# 05-UARTBridge.net
KiCad netlist of a schematic drawn in Altium Designer
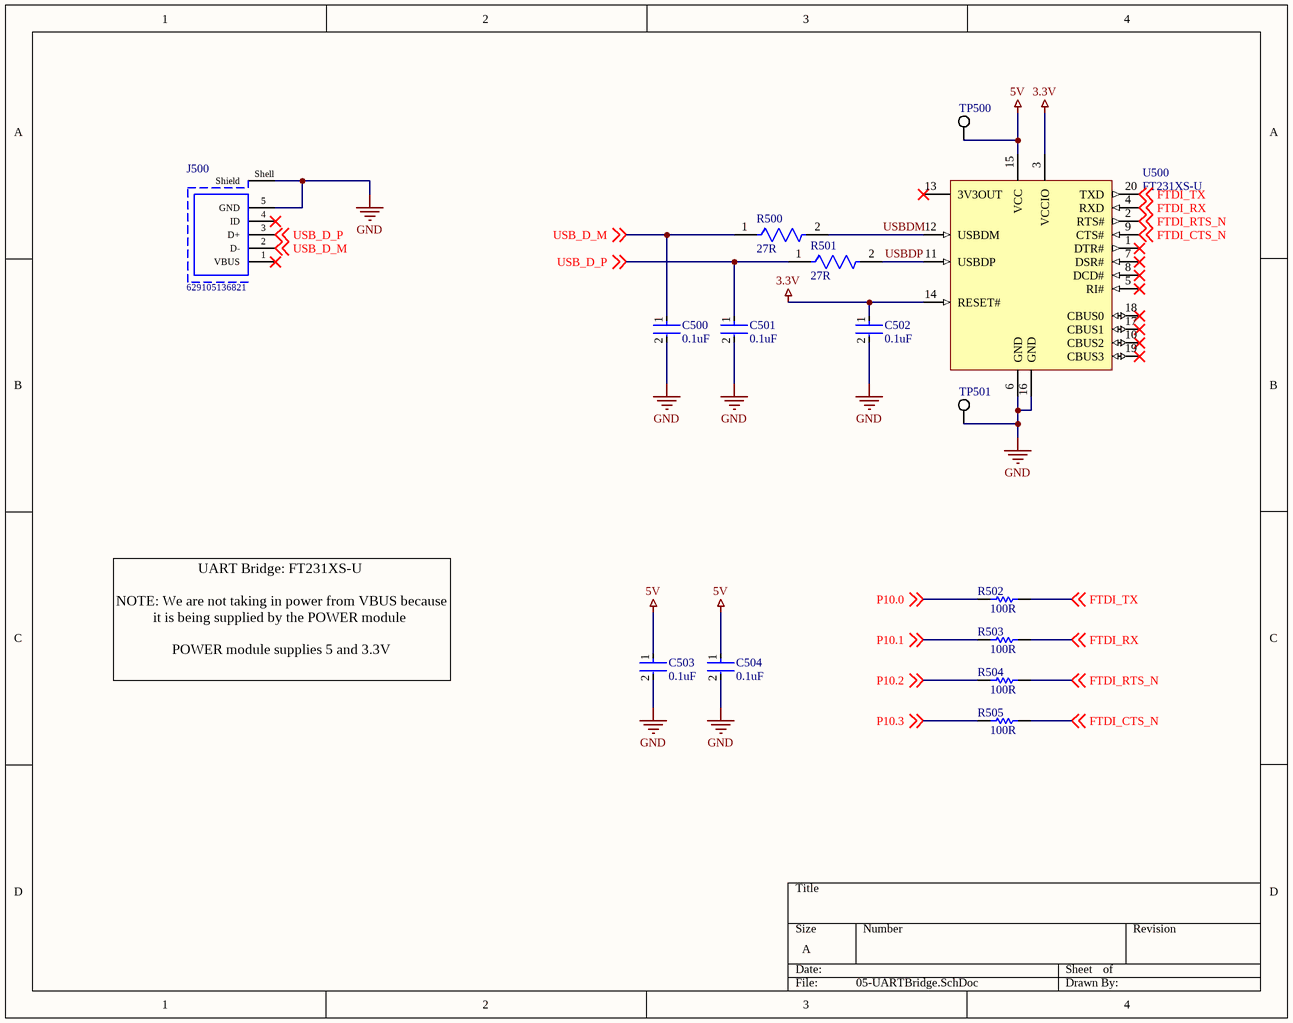
[diagram p0: 05-UARTBridge.SchDoc]

(export (version "E")
  (design (tool "Eeschema 10.0.6"))
  (components
    (comp (ref "C500")
      (value "0.1uF")
      (footprint "FP-CL21-IPC_C")
      (description "CL21 Series 0805 100nF 50V ±10% Tolerance X7R Multilayer Ceramic Chip Capacitor")
      (fields (field (name "TOLERANCE") "10%") (field (name "VOLTAGE") "50V"))
      (libsource (lib "Altium Content Vault") (part "b4654b650e69147ec39a6b967a45e02"))
    )
    (comp (ref "C501")
      (value "0.1uF")
      (footprint "FP-CL21-IPC_C")
      (description "CL21 Series 0805 100nF 50V ±10% Tolerance X7R Multilayer Ceramic Chip Capacitor")
      (fields (field (name "TOLERANCE") "10%") (field (name "VOLTAGE") "50V"))
      (libsource (lib "Altium Content Vault") (part "b4654b650e69147ec39a6b967a45e02"))
    )
    (comp (ref "C502")
      (value "0.1uF")
      (footprint "FP-CL21-IPC_C")
      (description "CL21 Series 0805 100nF 50V ±10% Tolerance X7R Multilayer Ceramic Chip Capacitor")
      (fields (field (name "TOLERANCE") "10%") (field (name "VOLTAGE") "50V"))
      (libsource (lib "Altium Content Vault") (part "b4654b650e69147ec39a6b967a45e02"))
    )
    (comp (ref "C503")
      (value "0.1uF")
      (footprint "FP-CL21-IPC_C")
      (description "CL21 Series 0805 100nF 50V ±10% Tolerance X7R Multilayer Ceramic Chip Capacitor")
      (fields (field (name "TOLERANCE") "10%") (field (name "VOLTAGE") "50V"))
      (libsource (lib "Altium Content Vault") (part "b4654b650e69147ec39a6b967a45e02"))
    )
    (comp (ref "C504")
      (value "0.1uF")
      (footprint "FP-CL21-IPC_C")
      (description "CL21 Series 0805 100nF 50V ±10% Tolerance X7R Multilayer Ceramic Chip Capacitor")
      (fields (field (name "TOLERANCE") "10%") (field (name "VOLTAGE") "50V"))
      (libsource (lib "Altium Content Vault") (part "b4654b650e69147ec39a6b967a45e02"))
    )
    (comp (ref "J500")
      (value "629105136821")
      (footprint "629105136821")
      (description "Micro USB 2.0 Type B Receptacle WR-COM, Horizontal, SMT, with Pads and Pegs")
      (fields (field (name "MANUFACTURER") "Wurth Elektronik") (field (name "PUBLISHER") "WurthElektronik"))
      (libsource (lib "Altium Content Vault") (part "WE-USB-5-1SHLD"))
    )
    (comp (ref "R500")
      (value "27R")
      (footprint "FP-CRGCQ0805-IPC_C")
      (description "CRGCQ0805 27Ω 0.125W ±200ppm/°C 1% 150V")
      (fields
        (field (name "MANUFACTURER") "TE Connectivity")
        (field (name "OCTOPART") "https://octopart.com/crgcq0805f27r-te+connectivity-91018166")
      )
      (libsource (lib "Altium Content Vault") (part "1029c3af85768c4190bb7ad29bc67b5"))
    )
    (comp (ref "R501")
      (value "27R")
      (footprint "FP-CRGCQ0805-IPC_C")
      (description "CRGCQ0805 27Ω 0.125W ±200ppm/°C 1% 150V")
      (fields
        (field (name "MANUFACTURER") "TE Connectivity")
        (field (name "OCTOPART") "https://octopart.com/crgcq0805f27r-te+connectivity-91018166")
      )
      (libsource (lib "Altium Content Vault") (part "1029c3af85768c4190bb7ad29bc67b5"))
    )
    (comp (ref "R502")
      (value "100R")
      (footprint "RESC2013X60X40ML20T25")
      (fields (field (name "MANUFACTURER") "Panasonic") (field (name "PART NUMBER") "ERA6AEB101V"))
      (libsource (lib "Altium Content Vault") (part "RES"))
    )
    (comp (ref "R503")
      (value "100R")
      (footprint "RESC2013X60X40ML20T25")
      (fields (field (name "MANUFACTURER") "Panasonic") (field (name "PART NUMBER") "ERA6AEB101V"))
      (libsource (lib "Altium Content Vault") (part "RES"))
    )
    (comp (ref "R504")
      (value "100R")
      (footprint "RESC2013X60X40ML20T25")
      (fields (field (name "MANUFACTURER") "Panasonic") (field (name "PART NUMBER") "ERA6AEB101V"))
      (libsource (lib "Altium Content Vault") (part "RES"))
    )
    (comp (ref "R505")
      (value "100R")
      (footprint "RESC2013X60X40ML20T25")
      (fields (field (name "MANUFACTURER") "Panasonic") (field (name "PART NUMBER") "ERA6AEB101V"))
      (libsource (lib "Altium Content Vault") (part "RES"))
    )
    (comp (ref "TP500")
      (value "5019")
      (footprint "KSTN-5019_V")
      (description "Test Point, 1 Position SMD, RoHS, Tape and Reel")
      (libsource (lib "Altium Content Vault") (part "TESTPOINT_WHITE"))
    )
    (comp (ref "TP501")
      (value "5019")
      (footprint "KSTN-5019_V")
      (description "Test Point, 1 Position SMD, RoHS, Tape and Reel")
      (libsource (lib "Altium Content Vault") (part "TESTPOINT_WHITE"))
    )
    (comp (ref "U500")
      (value "FT231XS-U")
      (footprint "SSOP-20_L")
      (fields (field (name "MANUFACTURER") "FTDI"))
      (libsource (lib "Altium Content Vault") (part "COM-USB-FT231XS-IL20"))
    )
  )
  (nets
    (net (code "1") (name "/USBDM") (class "Default")
      (node (ref "R500") (pin "2") (pinfunction "2_2") (pintype "passive"))
      (node (ref "U500") (pin "12") (pinfunction "USBDM_12") (pintype "input"))
    )
    (net (code "2") (name "/USBDP") (class "Default")
      (node (ref "R501") (pin "2") (pinfunction "2_2") (pintype "passive"))
      (node (ref "U500") (pin "11") (pinfunction "USBDP_11") (pintype "input"))
    )
    (net (code "3") (name "3.3V") (class "Default")
      (node (ref "C502") (pin "1") (pinfunction "1_1") (pintype "passive"))
      (node (ref "U500") (pin "14") (pinfunction "RESET#_14") (pintype "input"))
      (node (ref "U500") (pin "3") (pinfunction "VCCIO_3") (pintype "power_in"))
    )
    (net (code "4") (name "5V") (class "Default")
      (node (ref "C503") (pin "1") (pinfunction "1_1") (pintype "passive"))
      (node (ref "C504") (pin "1") (pinfunction "1_1") (pintype "passive"))
      (node (ref "TP500") (pin "1") (pinfunction "1_1") (pintype "passive"))
      (node (ref "U500") (pin "15") (pinfunction "VCC_15") (pintype "power_in"))
    )
    (net (code "5") (name "FTDI_CTS_N") (class "Default")
      (node (ref "R505") (pin "2") (pinfunction "2_2") (pintype "passive"))
      (node (ref "U500") (pin "9") (pinfunction "CTS#_9") (pintype "input"))
    )
    (net (code "6") (name "FTDI_RTS_N") (class "Default")
      (node (ref "R504") (pin "2") (pinfunction "2_2") (pintype "passive"))
      (node (ref "U500") (pin "2") (pinfunction "RTS#_2") (pintype "output"))
    )
    (net (code "7") (name "FTDI_RX") (class "Default")
      (node (ref "R503") (pin "2") (pinfunction "2_2") (pintype "passive"))
      (node (ref "U500") (pin "4") (pinfunction "RXD_4") (pintype "input"))
    )
    (net (code "8") (name "FTDI_TX") (class "Default")
      (node (ref "R502") (pin "2") (pinfunction "2_2") (pintype "passive"))
      (node (ref "U500") (pin "20") (pinfunction "TXD_20") (pintype "output"))
    )
    (net (code "9") (name "GND") (class "Default")
      (node (ref "C500") (pin "2") (pinfunction "2_2") (pintype "passive"))
      (node (ref "C501") (pin "2") (pinfunction "2_2") (pintype "passive"))
      (node (ref "C502") (pin "2") (pinfunction "2_2") (pintype "passive"))
      (node (ref "C503") (pin "2") (pinfunction "2_2") (pintype "passive"))
      (node (ref "C504") (pin "2") (pinfunction "2_2") (pintype "passive"))
      (node (ref "J500") (pin "5") (pinfunction "GND_5") (pintype "passive"))
      (node (ref "J500") (pin "Shell") (pinfunction "Shield_Shell") (pintype "passive"))
      (node (ref "TP501") (pin "1") (pinfunction "1_1") (pintype "passive"))
      (node (ref "U500") (pin "16") (pinfunction "GND_16") (pintype "power_in"))
      (node (ref "U500") (pin "6") (pinfunction "GND_6") (pintype "power_in"))
    )
    (net (code "10") (name "P10.0") (class "Default")
      (node (ref "R502") (pin "1") (pinfunction "1_1") (pintype "passive"))
    )
    (net (code "11") (name "P10.1") (class "Default")
      (node (ref "R503") (pin "1") (pinfunction "1_1") (pintype "passive"))
    )
    (net (code "12") (name "P10.2") (class "Default")
      (node (ref "R504") (pin "1") (pinfunction "1_1") (pintype "passive"))
    )
    (net (code "13") (name "P10.3") (class "Default")
      (node (ref "R505") (pin "1") (pinfunction "1_1") (pintype "passive"))
    )
    (net (code "14") (name "USB_D_M") (class "Default")
      (node (ref "C500") (pin "1") (pinfunction "1_1") (pintype "passive"))
      (node (ref "J500") (pin "2") (pinfunction "D-_2") (pintype "passive"))
      (node (ref "R500") (pin "1") (pinfunction "1_1") (pintype "passive"))
    )
    (net (code "15") (name "USB_D_P") (class "Default")
      (node (ref "C501") (pin "1") (pinfunction "1_1") (pintype "passive"))
      (node (ref "J500") (pin "3") (pinfunction "D+_3") (pintype "passive"))
      (node (ref "R501") (pin "1") (pinfunction "1_1") (pintype "passive"))
    )
    (net (code "16") (name "unconnected-(J500-ID-Pad4)") (class "Default")
      (node (ref "J500") (pin "4") (pinfunction "ID_4") (pintype "passive+no_connect"))
    )
    (net (code "17") (name "unconnected-(J500-VBUS-Pad1)") (class "Default")
      (node (ref "J500") (pin "1") (pinfunction "VBUS_1") (pintype "passive+no_connect"))
    )
    (net (code "18") (name "unconnected-(U500-3V3OUT-Pad13)") (class "Default")
      (node (ref "U500") (pin "13") (pinfunction "3V3OUT_13") (pintype "power_in+no_connect"))
    )
    (net (code "19") (name "unconnected-(U500-CBUS0-Pad18)") (class "Default")
      (node (ref "U500") (pin "18") (pinfunction "CBUS0_18") (pintype "bidirectional+no_connect"))
    )
    (net (code "20") (name "unconnected-(U500-CBUS1-Pad17)") (class "Default")
      (node (ref "U500") (pin "17") (pinfunction "CBUS1_17") (pintype "bidirectional+no_connect"))
    )
    (net (code "21") (name "unconnected-(U500-CBUS2-Pad10)") (class "Default")
      (node (ref "U500") (pin "10") (pinfunction "CBUS2_10") (pintype "bidirectional+no_connect"))
    )
    (net (code "22") (name "unconnected-(U500-CBUS3-Pad19)") (class "Default")
      (node (ref "U500") (pin "19") (pinfunction "CBUS3_19") (pintype "bidirectional+no_connect"))
    )
    (net (code "23") (name "unconnected-(U500-DCD#-Pad8)") (class "Default")
      (node (ref "U500") (pin "8") (pinfunction "DCD#_8") (pintype "input+no_connect"))
    )
    (net (code "24") (name "unconnected-(U500-DSR#-Pad7)") (class "Default")
      (node (ref "U500") (pin "7") (pinfunction "DSR#_7") (pintype "input+no_connect"))
    )
    (net (code "25") (name "unconnected-(U500-DTR#-Pad1)") (class "Default")
      (node (ref "U500") (pin "1") (pinfunction "DTR#_1") (pintype "output+no_connect"))
    )
    (net (code "26") (name "unconnected-(U500-RI#-Pad5)") (class "Default")
      (node (ref "U500") (pin "5") (pinfunction "RI#_5") (pintype "input+no_connect"))
    )
  )
)
